# PowerSupply.net
KiCad netlist of a schematic drawn in Altium Designer
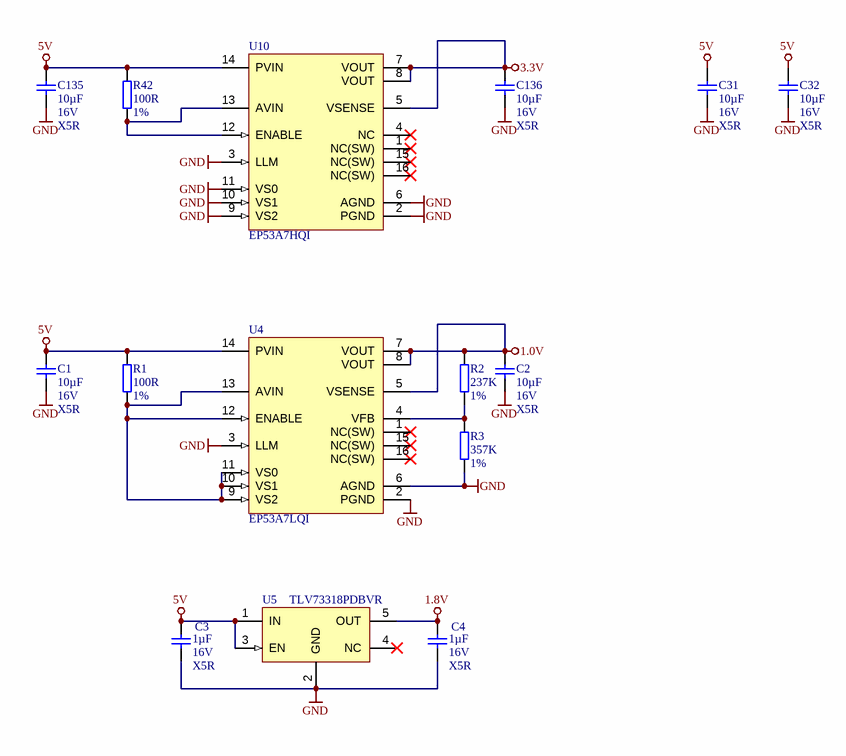
[diagram p0: PowerSupply.SchDoc]

(export (version "E")
  (design (tool "Eeschema 10.0.6"))
  (components
    (comp (ref "C1")
      (value "10µF")
      (footprint "CAPC1608X90N")
      (description "KON 10µF 16V X5R 20% SMD BF 1608 (0603)")
      (fields
        (field (name "VOLTAGE") "16V")
        (field (name "TECHNOLOGY") "X5R")
        (field (name "TOLERANCE") "20%")
      )
      (libsource (lib "TE") (part "CAP-NP"))
    )
    (comp (ref "C2")
      (value "10µF")
      (footprint "CAPC1608X90N")
      (description "KON 10µF 16V X5R 20% SMD BF 1608 (0603)")
      (fields
        (field (name "VOLTAGE") "16V")
        (field (name "TECHNOLOGY") "X5R")
        (field (name "TOLERANCE") "20%")
      )
      (libsource (lib "TE") (part "CAP-NP"))
    )
    (comp (ref "C3")
      (value "1µF")
      (footprint "CAPC1005X55N")
      (description "KON 1µF 16V X5R 10% SMD BF 1005 (0402)")
      (fields
        (field (name "VOLTAGE") "16V")
        (field (name "TECHNOLOGY") "X5R")
        (field (name "TOLERANCE") "10%")
      )
      (libsource (lib "TE") (part "CAP-NP"))
    )
    (comp (ref "C4")
      (value "1µF")
      (footprint "CAPC1005X55N")
      (description "KON 1µF 16V X5R 10% SMD BF 1005 (0402)")
      (fields
        (field (name "VOLTAGE") "16V")
        (field (name "TECHNOLOGY") "X5R")
        (field (name "TOLERANCE") "10%")
      )
      (libsource (lib "TE") (part "CAP-NP"))
    )
    (comp (ref "C31")
      (value "10µF")
      (footprint "CAPC1608X90N")
      (description "KON 10µF 16V X5R 20% SMD BF 1608 (0603)")
      (fields
        (field (name "VOLTAGE") "16V")
        (field (name "TECHNOLOGY") "X5R")
        (field (name "TOLERANCE") "20%")
      )
      (libsource (lib "TE") (part "CAP-NP"))
    )
    (comp (ref "C32")
      (value "10µF")
      (footprint "CAPC1608X90N")
      (description "KON 10µF 16V X5R 20% SMD BF 1608 (0603)")
      (fields
        (field (name "VOLTAGE") "16V")
        (field (name "TECHNOLOGY") "X5R")
        (field (name "TOLERANCE") "20%")
      )
      (libsource (lib "TE") (part "CAP-NP"))
    )
    (comp (ref "C135")
      (value "10µF")
      (footprint "CAPC1608X90N")
      (description "KON 10µF 16V X5R 20% SMD BF 1608 (0603)")
      (fields
        (field (name "VOLTAGE") "16V")
        (field (name "TECHNOLOGY") "X5R")
        (field (name "TOLERANCE") "20%")
      )
      (libsource (lib "TE") (part "CAP-NP"))
    )
    (comp (ref "C136")
      (value "10µF")
      (footprint "CAPC1608X90N")
      (description "KON 10µF 16V X5R 20% SMD BF 1608 (0603)")
      (fields
        (field (name "VOLTAGE") "16V")
        (field (name "TECHNOLOGY") "X5R")
        (field (name "TOLERANCE") "20%")
      )
      (libsource (lib "TE") (part "CAP-NP"))
    )
    (comp (ref "R1")
      (value "100R")
      (footprint "RESC1005X40N")
      (description "WID SMD 100R 1% 0,063W  BF 1005 (0402)")
      (fields (field (name "TOLERANCE") "1%"))
      (libsource (lib "TE") (part "RES"))
    )
    (comp (ref "R2")
      (value "237K")
      (footprint "RESC1005X40N")
      (description "WID SMD 237K 1% 0,063W")
      (fields (field (name "TOLERANCE") "1%"))
      (libsource (lib "TE") (part "RES"))
    )
    (comp (ref "R3")
      (value "357K")
      (footprint "RESC1005X40N")
      (description "WID SMD 357K 1% 0,063W")
      (fields (field (name "TOLERANCE") "1%"))
      (libsource (lib "TE") (part "RES"))
    )
    (comp (ref "R42")
      (value "100R")
      (footprint "RESC1005X40N")
      (description "WID SMD 100R 1% 0,063W  BF 1005 (0402)")
      (fields (field (name "TOLERANCE") "1%"))
      (libsource (lib "TE") (part "RES"))
    )
    (comp (ref "U4") (value "EP53A7LQI") (footprint "EP53F8QI") (libsource (lib "TE") (part "EP53A7LQI")))
    (comp (ref "U5")
      (value "TLV73318PDBVR")
      (footprint "SOT95P280X145-5N")
      (description "TLV73318PDBV")
      (fields (field (name "VOLTAGE") "1.8V"))
      (libsource (lib "TE") (part "TLV70235DBV"))
    )
    (comp (ref "U10") (value "EP53A7HQI") (footprint "EP53F8QI") (libsource (lib "TE") (part "EP53A7HQI")))
  )
  (nets
    (net (code "1") (name "1.0V") (class "Default")
      (node (ref "C2") (pin "2") (pinfunction "2_2") (pintype "passive"))
      (node (ref "R2") (pin "1") (pinfunction "1_1") (pintype "passive"))
      (node (ref "U4") (pin "5") (pinfunction "VSENSE_5") (pintype "passive"))
      (node (ref "U4") (pin "7") (pinfunction "VOUT_7") (pintype "power_in"))
      (node (ref "U4") (pin "8") (pinfunction "VOUT_8") (pintype "power_in"))
    )
    (net (code "2") (name "1.8V") (class "Default")
      (node (ref "C4") (pin "1") (pinfunction "1_1") (pintype "passive"))
      (node (ref "U5") (pin "5") (pinfunction "OUT_5") (pintype "power_in"))
    )
    (net (code "3") (name "3.3V") (class "Default")
      (node (ref "C136") (pin "2") (pinfunction "2_2") (pintype "passive"))
      (node (ref "U10") (pin "5") (pinfunction "VSENSE_5") (pintype "passive"))
      (node (ref "U10") (pin "7") (pinfunction "VOUT_7") (pintype "power_in"))
      (node (ref "U10") (pin "8") (pinfunction "VOUT_8") (pintype "power_in"))
    )
    (net (code "4") (name "5V") (class "Default")
      (node (ref "C1") (pin "2") (pinfunction "2_2") (pintype "passive"))
      (node (ref "C135") (pin "2") (pinfunction "2_2") (pintype "passive"))
      (node (ref "C3") (pin "1") (pinfunction "1_1") (pintype "passive"))
      (node (ref "C31") (pin "2") (pinfunction "2_2") (pintype "passive"))
      (node (ref "C32") (pin "2") (pinfunction "2_2") (pintype "passive"))
      (node (ref "R1") (pin "1") (pinfunction "1_1") (pintype "passive"))
      (node (ref "R42") (pin "1") (pinfunction "1_1") (pintype "passive"))
      (node (ref "U10") (pin "14") (pinfunction "PVIN_14") (pintype "power_in"))
      (node (ref "U4") (pin "14") (pinfunction "PVIN_14") (pintype "power_in"))
      (node (ref "U5") (pin "1") (pinfunction "IN_1") (pintype "power_in"))
      (node (ref "U5") (pin "3") (pinfunction "EN_3") (pintype "input"))
    )
    (net (code "5") (name "GND") (class "Default")
      (node (ref "C1") (pin "1") (pinfunction "1_1") (pintype "passive"))
      (node (ref "C135") (pin "1") (pinfunction "1_1") (pintype "passive"))
      (node (ref "C136") (pin "1") (pinfunction "1_1") (pintype "passive"))
      (node (ref "C2") (pin "1") (pinfunction "1_1") (pintype "passive"))
      (node (ref "C3") (pin "2") (pinfunction "2_2") (pintype "passive"))
      (node (ref "C31") (pin "1") (pinfunction "1_1") (pintype "passive"))
      (node (ref "C32") (pin "1") (pinfunction "1_1") (pintype "passive"))
      (node (ref "C4") (pin "2") (pinfunction "2_2") (pintype "passive"))
      (node (ref "R3") (pin "2") (pinfunction "2_2") (pintype "passive"))
      (node (ref "U10") (pin "10") (pinfunction "VS1_10") (pintype "input"))
      (node (ref "U10") (pin "11") (pinfunction "VS0_11") (pintype "input"))
      (node (ref "U10") (pin "2") (pinfunction "PGND_2") (pintype "power_in"))
      (node (ref "U10") (pin "3") (pinfunction "LLM_3") (pintype "input"))
      (node (ref "U10") (pin "6") (pinfunction "AGND_6") (pintype "power_in"))
      (node (ref "U10") (pin "9") (pinfunction "VS2_9") (pintype "input"))
      (node (ref "U4") (pin "2") (pinfunction "PGND_2") (pintype "power_in"))
      (node (ref "U4") (pin "3") (pinfunction "LLM_3") (pintype "input"))
      (node (ref "U4") (pin "6") (pinfunction "AGND_6") (pintype "power_in"))
      (node (ref "U5") (pin "2") (pinfunction "GND_2") (pintype "power_in"))
    )
    (net (code "6") (name "Net-(U4-AVIN)") (class "Default")
      (node (ref "R1") (pin "2") (pinfunction "2_2") (pintype "passive"))
      (node (ref "U4") (pin "10") (pinfunction "VS1_10") (pintype "input"))
      (node (ref "U4") (pin "11") (pinfunction "VS0_11") (pintype "input"))
      (node (ref "U4") (pin "12") (pinfunction "ENABLE_12") (pintype "input"))
      (node (ref "U4") (pin "13") (pinfunction "AVIN_13") (pintype "power_in"))
      (node (ref "U4") (pin "9") (pinfunction "VS2_9") (pintype "input"))
    )
    (net (code "7") (name "Net-(U4-VFB)") (class "Default")
      (node (ref "R2") (pin "2") (pinfunction "2_2") (pintype "passive"))
      (node (ref "R3") (pin "1") (pinfunction "1_1") (pintype "passive"))
      (node (ref "U4") (pin "4") (pinfunction "VFB_4") (pintype "passive"))
    )
    (net (code "8") (name "Net-(U10-AVIN)") (class "Default")
      (node (ref "R42") (pin "2") (pinfunction "2_2") (pintype "passive"))
      (node (ref "U10") (pin "12") (pinfunction "ENABLE_12") (pintype "input"))
      (node (ref "U10") (pin "13") (pinfunction "AVIN_13") (pintype "power_in"))
    )
    (net (code "9") (name "unconnected-(U4-NC(SW)-Pad1)") (class "Default")
      (node (ref "U4") (pin "1") (pinfunction "NC(SW)_1") (pintype "passive+no_connect"))
    )
    (net (code "10") (name "unconnected-(U4-NC(SW)-Pad15)") (class "Default")
      (node (ref "U4") (pin "15") (pinfunction "NC(SW)_15") (pintype "passive+no_connect"))
    )
    (net (code "11") (name "unconnected-(U4-NC(SW)-Pad16)") (class "Default")
      (node (ref "U4") (pin "16") (pinfunction "NC(SW)_16") (pintype "passive+no_connect"))
    )
    (net (code "12") (name "unconnected-(U5-NC-Pad4)") (class "Default")
      (node (ref "U5") (pin "4") (pinfunction "NC_4") (pintype "passive+no_connect"))
    )
    (net (code "13") (name "unconnected-(U10-NC(SW)-Pad1)") (class "Default")
      (node (ref "U10") (pin "1") (pinfunction "NC(SW)_1") (pintype "passive+no_connect"))
    )
    (net (code "14") (name "unconnected-(U10-NC(SW)-Pad15)") (class "Default")
      (node (ref "U10") (pin "15") (pinfunction "NC(SW)_15") (pintype "passive+no_connect"))
    )
    (net (code "15") (name "unconnected-(U10-NC(SW)-Pad16)") (class "Default")
      (node (ref "U10") (pin "16") (pinfunction "NC(SW)_16") (pintype "passive+no_connect"))
    )
    (net (code "16") (name "unconnected-(U10-NC-Pad4)") (class "Default")
      (node (ref "U10") (pin "4") (pinfunction "NC_4") (pintype "passive+no_connect"))
    )
  )
)
